# LED_chaser_schematics.net
KiCad netlist of a schematic drawn in EAGLE
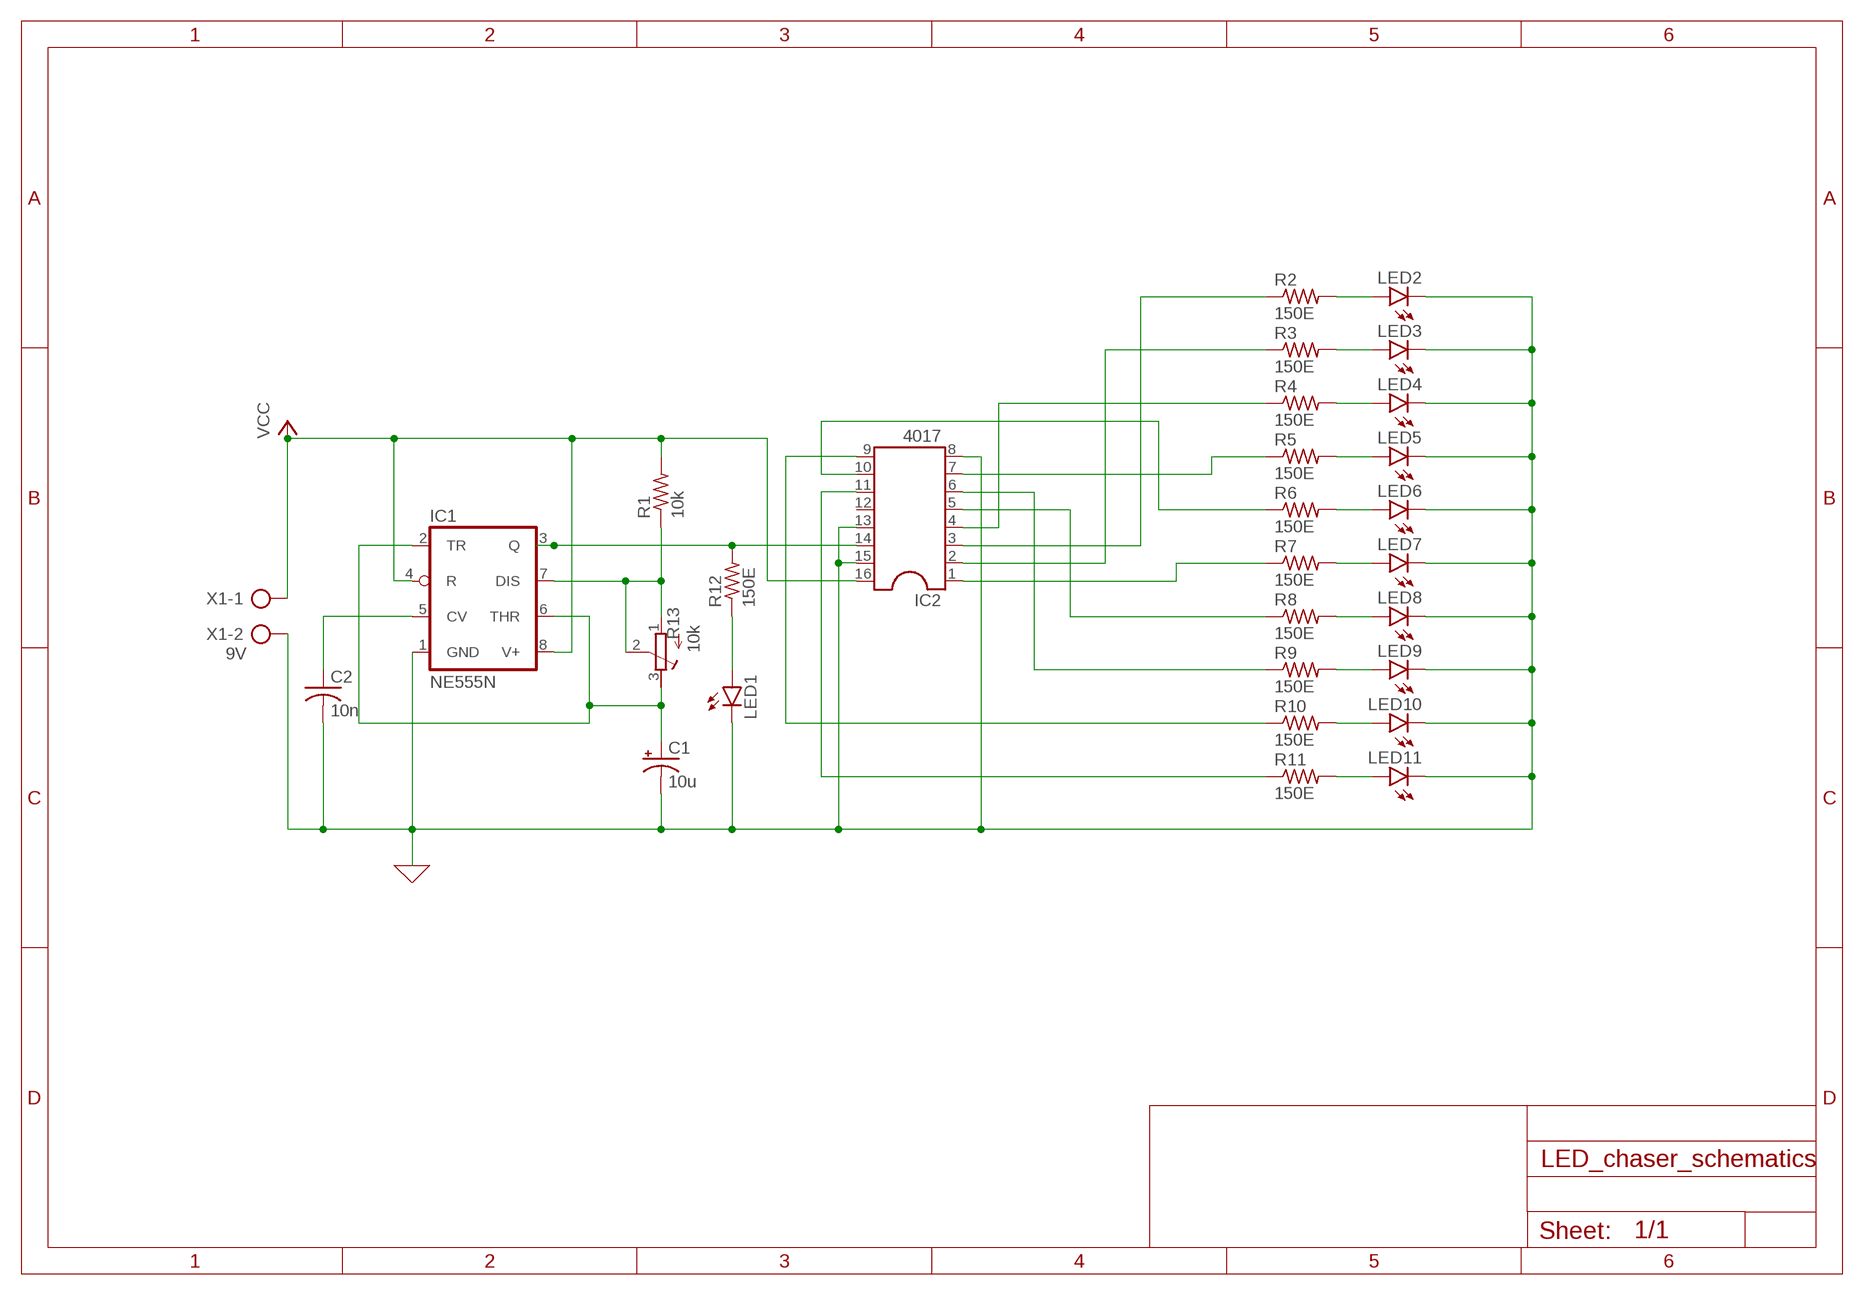
[diagram p0: schematic, sheet 1]

(export (version "E")
  (design (tool "Eeschema 10.0.6"))
  (components
    (comp (ref "C1")
      (value "10u")
      (footprint "eagle-import:E2,5-6")
      (libsource (lib "eagle-import") (part "CPOL-USE2.5-6"))
    )
    (comp (ref "C2")
      (value "10n")
      (footprint "eagle-import:C025-024X044")
      (libsource (lib "eagle-import") (part "C-US025-024X044"))
    )
    (comp (ref "IC1")
      (value "NE555N")
      (footprint "eagle-import:DIL08")
      (libsource (lib "eagle-import") (part "555NNE"))
    )
    (comp (ref "IC2")
      (value "4017")
      (footprint "eagle-import:DIL16")
      (libsource (lib "eagle-import") (part "DIL16"))
    )
    (comp (ref "LED1")
      (value "LED5MM")
      (footprint "eagle-import:LED5MM")
      (libsource (lib "eagle-import") (part "LED5MM"))
    )
    (comp (ref "LED2")
      (value "LED5MM")
      (footprint "eagle-import:LED5MM")
      (libsource (lib "eagle-import") (part "LED5MM"))
    )
    (comp (ref "LED3")
      (value "LED5MM")
      (footprint "eagle-import:LED5MM")
      (libsource (lib "eagle-import") (part "LED5MM"))
    )
    (comp (ref "LED4")
      (value "LED5MM")
      (footprint "eagle-import:LED5MM")
      (libsource (lib "eagle-import") (part "LED5MM"))
    )
    (comp (ref "LED5")
      (value "LED5MM")
      (footprint "eagle-import:LED5MM")
      (libsource (lib "eagle-import") (part "LED5MM"))
    )
    (comp (ref "LED6")
      (value "LED5MM")
      (footprint "eagle-import:LED5MM")
      (libsource (lib "eagle-import") (part "LED5MM"))
    )
    (comp (ref "LED7")
      (value "LED5MM")
      (footprint "eagle-import:LED5MM")
      (libsource (lib "eagle-import") (part "LED5MM"))
    )
    (comp (ref "LED8")
      (value "LED5MM")
      (footprint "eagle-import:LED5MM")
      (libsource (lib "eagle-import") (part "LED5MM"))
    )
    (comp (ref "LED9")
      (value "LED5MM")
      (footprint "eagle-import:LED5MM")
      (libsource (lib "eagle-import") (part "LED5MM"))
    )
    (comp (ref "LED10")
      (value "LED5MM")
      (footprint "eagle-import:LED5MM")
      (libsource (lib "eagle-import") (part "LED5MM"))
    )
    (comp (ref "LED11")
      (value "LED5MM")
      (footprint "eagle-import:LED5MM")
      (libsource (lib "eagle-import") (part "LED5MM"))
    )
    (comp (ref "R1")
      (value "10k")
      (footprint "eagle-import:0207_10")
      (libsource (lib "eagle-import") (part "R-US_0207/10"))
    )
    (comp (ref "R2")
      (value "150E")
      (footprint "eagle-import:0207_10")
      (libsource (lib "eagle-import") (part "R-US_0207/10"))
    )
    (comp (ref "R3")
      (value "150E")
      (footprint "eagle-import:0207_10")
      (libsource (lib "eagle-import") (part "R-US_0207/10"))
    )
    (comp (ref "R4")
      (value "150E")
      (footprint "eagle-import:0207_10")
      (libsource (lib "eagle-import") (part "R-US_0207/10"))
    )
    (comp (ref "R5")
      (value "150E")
      (footprint "eagle-import:0207_10")
      (libsource (lib "eagle-import") (part "R-US_0207/10"))
    )
    (comp (ref "R6")
      (value "150E")
      (footprint "eagle-import:0207_10")
      (libsource (lib "eagle-import") (part "R-US_0207/10"))
    )
    (comp (ref "R7")
      (value "150E")
      (footprint "eagle-import:0207_10")
      (libsource (lib "eagle-import") (part "R-US_0207/10"))
    )
    (comp (ref "R8")
      (value "150E")
      (footprint "eagle-import:0207_10")
      (libsource (lib "eagle-import") (part "R-US_0207/10"))
    )
    (comp (ref "R9")
      (value "150E")
      (footprint "eagle-import:0207_10")
      (libsource (lib "eagle-import") (part "R-US_0207/10"))
    )
    (comp (ref "R10")
      (value "150E")
      (footprint "eagle-import:0207_10")
      (libsource (lib "eagle-import") (part "R-US_0207/10"))
    )
    (comp (ref "R11")
      (value "150E")
      (footprint "eagle-import:0207_10")
      (libsource (lib "eagle-import") (part "R-US_0207/10"))
    )
    (comp (ref "R12")
      (value "150E")
      (footprint "eagle-import:0207_10")
      (libsource (lib "eagle-import") (part "R-US_0207/10"))
    )
    (comp (ref "R13")
      (value "10k")
      (footprint "eagle-import:RTRIM3299W")
      (libsource (lib "eagle-import") (part "R-TRIMM3299W"))
    )
    (comp (ref "X1")
      (value "9V")
      (footprint "eagle-import:AK500_2")
      (libsource (lib "eagle-import") (part "AK500/2"))
    )
  )
  (nets
    (net (code "1") (name "GND") (class "Default")
      (node (ref "C1") (pin "-") (pinfunction "-_-") (pintype "passive"))
      (node (ref "C2") (pin "2") (pinfunction "2_2") (pintype "passive"))
      (node (ref "IC1") (pin "1") (pinfunction "GND_1") (pintype "power_in"))
      (node (ref "IC2") (pin "13") (pinfunction "13_13") (pintype "passive"))
      (node (ref "IC2") (pin "15") (pinfunction "15_15") (pintype "passive"))
      (node (ref "IC2") (pin "8") (pinfunction "8_8") (pintype "passive"))
      (node (ref "LED1") (pin "K") (pinfunction "C_K") (pintype "passive"))
      (node (ref "LED10") (pin "K") (pinfunction "C_K") (pintype "passive"))
      (node (ref "LED11") (pin "K") (pinfunction "C_K") (pintype "passive"))
      (node (ref "LED2") (pin "K") (pinfunction "C_K") (pintype "passive"))
      (node (ref "LED3") (pin "K") (pinfunction "C_K") (pintype "passive"))
      (node (ref "LED4") (pin "K") (pinfunction "C_K") (pintype "passive"))
      (node (ref "LED5") (pin "K") (pinfunction "C_K") (pintype "passive"))
      (node (ref "LED6") (pin "K") (pinfunction "C_K") (pintype "passive"))
      (node (ref "LED7") (pin "K") (pinfunction "C_K") (pintype "passive"))
      (node (ref "LED8") (pin "K") (pinfunction "C_K") (pintype "passive"))
      (node (ref "LED9") (pin "K") (pinfunction "C_K") (pintype "passive"))
      (node (ref "X1") (pin "2") (pinfunction "KL_2") (pintype "passive"))
    )
    (net (code "2") (name "Net-(IC1-CV)") (class "Default")
      (node (ref "C2") (pin "1") (pinfunction "1_1") (pintype "passive"))
      (node (ref "IC1") (pin "5") (pinfunction "CV_5") (pintype "input"))
    )
    (net (code "3") (name "Net-(IC1-DIS)") (class "Default")
      (node (ref "IC1") (pin "7") (pinfunction "DIS_7") (pintype "input"))
      (node (ref "R1") (pin "1") (pinfunction "1_1") (pintype "passive"))
      (node (ref "R13") (pin "1") (pinfunction "A_1") (pintype "passive"))
      (node (ref "R13") (pin "2") (pinfunction "S_2") (pintype "passive"))
    )
    (net (code "4") (name "Net-(IC1-Q)") (class "Default")
      (node (ref "IC1") (pin "3") (pinfunction "Q_3") (pintype "output"))
      (node (ref "IC2") (pin "14") (pinfunction "14_14") (pintype "passive"))
      (node (ref "R12") (pin "2") (pinfunction "2_2") (pintype "passive"))
    )
    (net (code "5") (name "Net-(IC1-THR)") (class "Default")
      (node (ref "C1") (pin "+") (pinfunction "+_+") (pintype "passive"))
      (node (ref "IC1") (pin "2") (pinfunction "TR_2") (pintype "input"))
      (node (ref "IC1") (pin "6") (pinfunction "THR_6") (pintype "input"))
      (node (ref "R13") (pin "3") (pinfunction "E_3") (pintype "passive"))
    )
    (net (code "6") (name "Net-(IC2-Pad1)") (class "Default")
      (node (ref "IC2") (pin "1") (pinfunction "1_1") (pintype "passive"))
      (node (ref "R7") (pin "1") (pinfunction "1_1") (pintype "passive"))
    )
    (net (code "7") (name "Net-(IC2-Pad2)") (class "Default")
      (node (ref "IC2") (pin "2") (pinfunction "2_2") (pintype "passive"))
      (node (ref "R3") (pin "1") (pinfunction "1_1") (pintype "passive"))
    )
    (net (code "8") (name "Net-(IC2-Pad3)") (class "Default")
      (node (ref "IC2") (pin "3") (pinfunction "3_3") (pintype "passive"))
      (node (ref "R2") (pin "1") (pinfunction "1_1") (pintype "passive"))
    )
    (net (code "9") (name "Net-(IC2-Pad4)") (class "Default")
      (node (ref "IC2") (pin "4") (pinfunction "4_4") (pintype "passive"))
      (node (ref "R4") (pin "1") (pinfunction "1_1") (pintype "passive"))
    )
    (net (code "10") (name "Net-(IC2-Pad5)") (class "Default")
      (node (ref "IC2") (pin "5") (pinfunction "5_5") (pintype "passive"))
      (node (ref "R8") (pin "1") (pinfunction "1_1") (pintype "passive"))
    )
    (net (code "11") (name "Net-(IC2-Pad6)") (class "Default")
      (node (ref "IC2") (pin "6") (pinfunction "6_6") (pintype "passive"))
      (node (ref "R9") (pin "1") (pinfunction "1_1") (pintype "passive"))
    )
    (net (code "12") (name "Net-(IC2-Pad7)") (class "Default")
      (node (ref "IC2") (pin "7") (pinfunction "7_7") (pintype "passive"))
      (node (ref "R5") (pin "1") (pinfunction "1_1") (pintype "passive"))
    )
    (net (code "13") (name "Net-(IC2-Pad9)") (class "Default")
      (node (ref "IC2") (pin "9") (pinfunction "9_9") (pintype "passive"))
      (node (ref "R10") (pin "1") (pinfunction "1_1") (pintype "passive"))
    )
    (net (code "14") (name "Net-(IC2-Pad10)") (class "Default")
      (node (ref "IC2") (pin "10") (pinfunction "10_10") (pintype "passive"))
      (node (ref "R6") (pin "1") (pinfunction "1_1") (pintype "passive"))
    )
    (net (code "15") (name "Net-(IC2-Pad11)") (class "Default")
      (node (ref "IC2") (pin "11") (pinfunction "11_11") (pintype "passive"))
      (node (ref "R11") (pin "1") (pinfunction "1_1") (pintype "passive"))
    )
    (net (code "16") (name "Net-(LED1-PadA)") (class "Default")
      (node (ref "LED1") (pin "A") (pinfunction "A_A") (pintype "passive"))
      (node (ref "R12") (pin "1") (pinfunction "1_1") (pintype "passive"))
    )
    (net (code "17") (name "Net-(LED2-PadA)") (class "Default")
      (node (ref "LED2") (pin "A") (pinfunction "A_A") (pintype "passive"))
      (node (ref "R2") (pin "2") (pinfunction "2_2") (pintype "passive"))
    )
    (net (code "18") (name "Net-(LED3-PadA)") (class "Default")
      (node (ref "LED3") (pin "A") (pinfunction "A_A") (pintype "passive"))
      (node (ref "R3") (pin "2") (pinfunction "2_2") (pintype "passive"))
    )
    (net (code "19") (name "Net-(LED4-PadA)") (class "Default")
      (node (ref "LED4") (pin "A") (pinfunction "A_A") (pintype "passive"))
      (node (ref "R4") (pin "2") (pinfunction "2_2") (pintype "passive"))
    )
    (net (code "20") (name "Net-(LED5-PadA)") (class "Default")
      (node (ref "LED5") (pin "A") (pinfunction "A_A") (pintype "passive"))
      (node (ref "R5") (pin "2") (pinfunction "2_2") (pintype "passive"))
    )
    (net (code "21") (name "Net-(LED6-PadA)") (class "Default")
      (node (ref "LED6") (pin "A") (pinfunction "A_A") (pintype "passive"))
      (node (ref "R6") (pin "2") (pinfunction "2_2") (pintype "passive"))
    )
    (net (code "22") (name "Net-(LED7-PadA)") (class "Default")
      (node (ref "LED7") (pin "A") (pinfunction "A_A") (pintype "passive"))
      (node (ref "R7") (pin "2") (pinfunction "2_2") (pintype "passive"))
    )
    (net (code "23") (name "Net-(LED8-PadA)") (class "Default")
      (node (ref "LED8") (pin "A") (pinfunction "A_A") (pintype "passive"))
      (node (ref "R8") (pin "2") (pinfunction "2_2") (pintype "passive"))
    )
    (net (code "24") (name "Net-(LED9-PadA)") (class "Default")
      (node (ref "LED9") (pin "A") (pinfunction "A_A") (pintype "passive"))
      (node (ref "R9") (pin "2") (pinfunction "2_2") (pintype "passive"))
    )
    (net (code "25") (name "Net-(LED10-PadA)") (class "Default")
      (node (ref "LED10") (pin "A") (pinfunction "A_A") (pintype "passive"))
      (node (ref "R10") (pin "2") (pinfunction "2_2") (pintype "passive"))
    )
    (net (code "26") (name "Net-(LED11-PadA)") (class "Default")
      (node (ref "LED11") (pin "A") (pinfunction "A_A") (pintype "passive"))
      (node (ref "R11") (pin "2") (pinfunction "2_2") (pintype "passive"))
    )
    (net (code "27") (name "VCC") (class "Default")
      (node (ref "IC1") (pin "4") (pinfunction "R_4") (pintype "input"))
      (node (ref "IC1") (pin "8") (pinfunction "V+_8") (pintype "power_in"))
      (node (ref "IC2") (pin "16") (pinfunction "16_16") (pintype "passive"))
      (node (ref "R1") (pin "2") (pinfunction "2_2") (pintype "passive"))
      (node (ref "X1") (pin "1") (pinfunction "KL_1") (pintype "passive"))
    )
    (net (code "28") (name "unconnected-(IC2-Pad12)") (class "Default")
      (node (ref "IC2") (pin "12") (pinfunction "12_12") (pintype "passive"))
    )
  )
)
